# MCU.net
KiCad netlist of a schematic drawn in Altium Designer
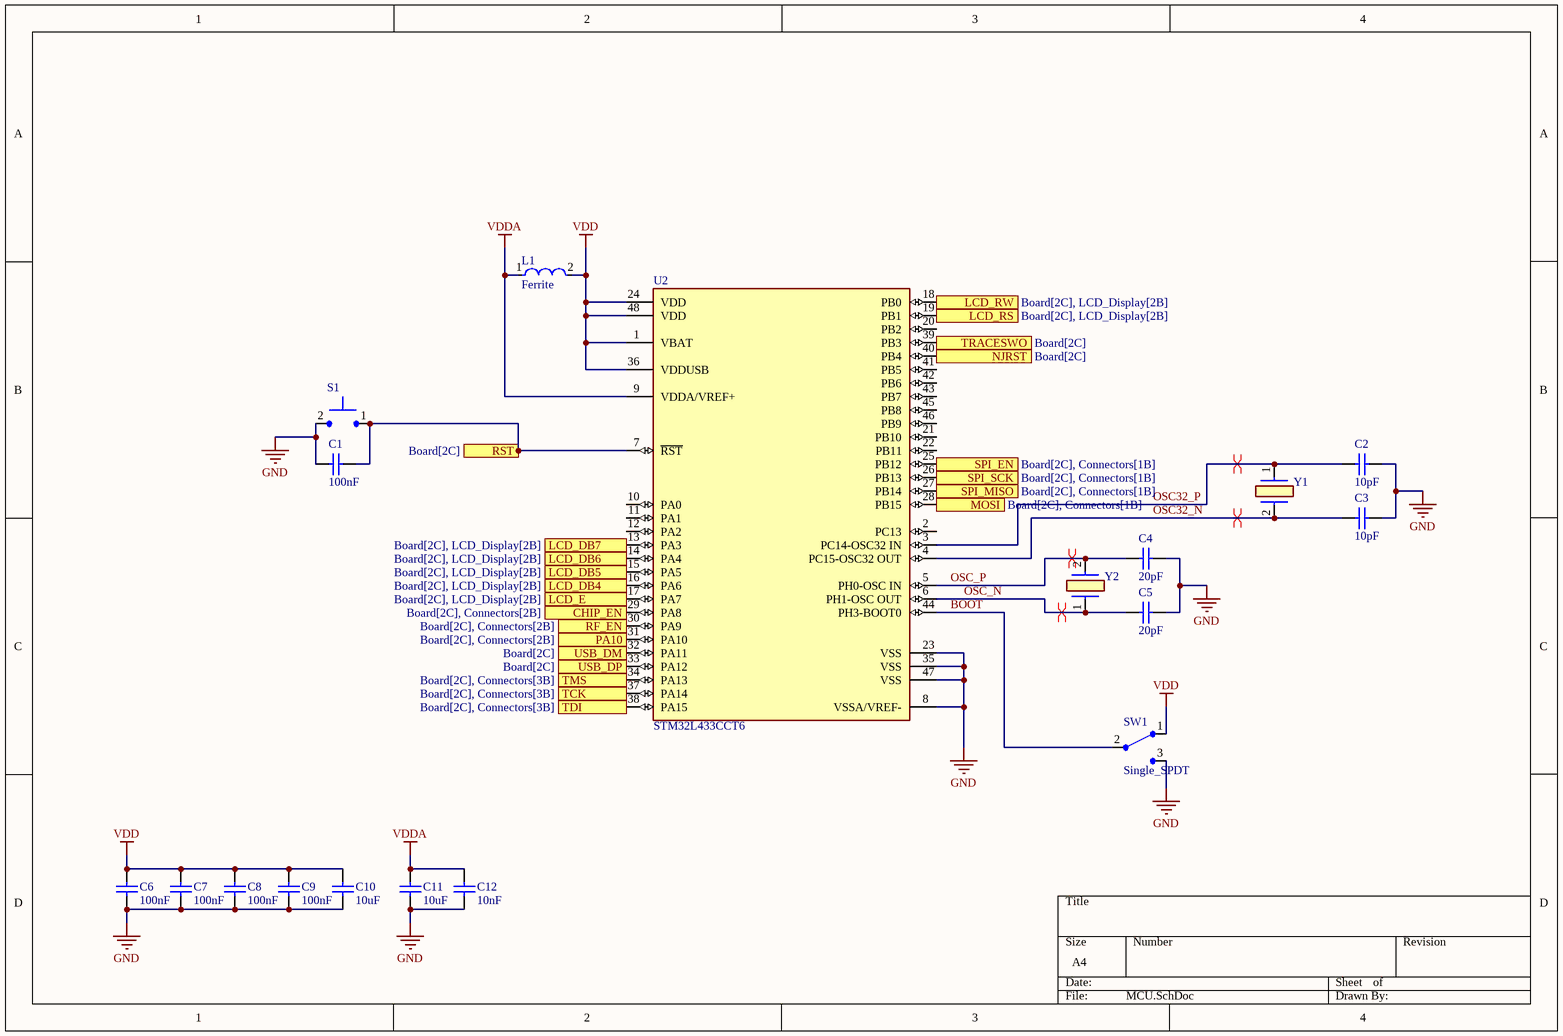
[diagram p0: MCU.SchDoc]

(export (version "E")
  (design (tool "Eeschema 10.0.6"))
  (components
    (comp (ref "C1")
      (value "100nF")
      (footprint "CAP_0402")
      (fields (field (name "MANUFACTURER") "Murata") (field (name "PART NUMBER") "GRM155R71E103KA01D"))
      (libsource (lib "schematics") (part "Capacitor"))
    )
    (comp (ref "C2")
      (value "10pF")
      (footprint "CAP_0402")
      (fields (field (name "MANUFACTURER") "Murata") (field (name "PART NUMBER") "GRM155R71E103KA01D"))
      (libsource (lib "schematics") (part "Capacitor"))
    )
    (comp (ref "C3")
      (value "10pF")
      (footprint "CAP_0402")
      (fields (field (name "MANUFACTURER") "Murata") (field (name "PART NUMBER") "GRM155R71E103KA01D"))
      (libsource (lib "schematics") (part "Capacitor"))
    )
    (comp (ref "C4")
      (value "20pF")
      (footprint "CAP_0402")
      (fields (field (name "MANUFACTURER") "Murata") (field (name "PART NUMBER") "GRM155R71E103KA01D"))
      (libsource (lib "schematics") (part "Capacitor"))
    )
    (comp (ref "C5")
      (value "20pF")
      (footprint "CAP_0402")
      (fields (field (name "MANUFACTURER") "Murata") (field (name "PART NUMBER") "GRM155R71E103KA01D"))
      (libsource (lib "schematics") (part "Capacitor"))
    )
    (comp (ref "C6")
      (value "100nF")
      (footprint "CAP_0402")
      (fields (field (name "MANUFACTURER") "Murata") (field (name "PART NUMBER") "GRM155R71E103KA01D"))
      (libsource (lib "schematics") (part "Capacitor"))
    )
    (comp (ref "C7")
      (value "100nF")
      (footprint "CAP_0402")
      (fields (field (name "MANUFACTURER") "Murata") (field (name "PART NUMBER") "GRM155R71E103KA01D"))
      (libsource (lib "schematics") (part "Capacitor"))
    )
    (comp (ref "C8")
      (value "100nF")
      (footprint "CAP_0402")
      (fields (field (name "MANUFACTURER") "Murata") (field (name "PART NUMBER") "GRM155R71E103KA01D"))
      (libsource (lib "schematics") (part "Capacitor"))
    )
    (comp (ref "C9")
      (value "100nF")
      (footprint "CAP_0402")
      (fields (field (name "MANUFACTURER") "Murata") (field (name "PART NUMBER") "GRM155R71E103KA01D"))
      (libsource (lib "schematics") (part "Capacitor"))
    )
    (comp (ref "C10")
      (value "10uF")
      (footprint "CAP_0402")
      (fields (field (name "MANUFACTURER") "Murata") (field (name "PART NUMBER") "GRM155R71E103KA01D"))
      (libsource (lib "schematics") (part "Capacitor"))
    )
    (comp (ref "C11")
      (value "10uF")
      (footprint "CAP_0402")
      (fields (field (name "MANUFACTURER") "Murata") (field (name "PART NUMBER") "GRM155R71E103KA01D"))
      (libsource (lib "schematics") (part "Capacitor"))
    )
    (comp (ref "C12")
      (value "10nF")
      (footprint "CAP_0402")
      (fields (field (name "MANUFACTURER") "Murata") (field (name "PART NUMBER") "GRM155R71E103KA01D"))
      (libsource (lib "schematics") (part "Capacitor"))
    )
    (comp (ref "L1")
      (value "Ferrite")
      (footprint "FP-LQW18AN_00-MFG")
      (fields (field (name "TOLERANCE") "2%"))
      (libsource (lib "schematics") (part "Ferrite_bead"))
    )
    (comp (ref "S1")
      (value "Generic 2-pin push button")
      (libsource (lib "schematics") (part "Push_btn_2pin"))
    )
    (comp (ref "SW1") (value "Single_SPDT") (libsource (lib "schematics") (part "Single_SPDT")))
    (comp (ref "U2")
      (value "STM32L433CCT6")
      (footprint "FP-LQFP48-5B-MFG")
      (description "IC MCU 32BIT 256KB FLASH 48LQFP")
      (fields
        (field (name "MANUFACTURER") "STMicroelectronics")
        (field (name "OCTOPART") "https://octopart.com/stm32l433cct6-stmicroelectronics-71093511")
      )
      (libsource (lib "schematics") (part "STM32L433CCT6"))
    )
    (comp (ref "Y1")
      (value "ECS-.320-12.5-13X")
      (footprint "SamacSys:ECS32012513X")
      (description "Crystal or Oscillator")
      (fields (field (name "MOUSER PART NUMBER") "520-ECS-32-12.5-13X"))
      (libsource (lib "schematics") (part "ECS-.320-12.5-13X"))
    )
    (comp (ref "Y2")
      (value "NX3225GD-8MHZ-STD-CRA-3")
      (footprint "SamacSys:NX3225GD8MHZSTDCRA3")
      (description "Crystal or Oscillator")
      (fields (field (name "MOUSER PART NUMBER") "344-NX3225GD8MCRA3"))
      (libsource (lib "schematics") (part "NX3225GD-8MHZ-STD-CRA-3"))
    )
  )
  (nets
    (net (code "1") (name "/BOOT") (class "Default")
      (node (ref "SW1") (pin "2") (pinfunction "2_2") (pintype "passive"))
      (node (ref "U2") (pin "44") (pinfunction "PH3-BOOT0_44") (pintype "bidirectional"))
    )
    (net (code "2") (name "/CHIP_EN") (class "Default")
      (node (ref "U2") (pin "29") (pinfunction "PA8_29") (pintype "bidirectional"))
    )
    (net (code "3") (name "/LCD_DB4") (class "Default")
      (node (ref "U2") (pin "16") (pinfunction "PA6_16") (pintype "bidirectional"))
    )
    (net (code "4") (name "/LCD_DB5") (class "Default")
      (node (ref "U2") (pin "15") (pinfunction "PA5_15") (pintype "bidirectional"))
    )
    (net (code "5") (name "/LCD_DB6") (class "Default")
      (node (ref "U2") (pin "14") (pinfunction "PA4_14") (pintype "bidirectional"))
    )
    (net (code "6") (name "/LCD_DB7") (class "Default")
      (node (ref "U2") (pin "13") (pinfunction "PA3_13") (pintype "bidirectional"))
    )
    (net (code "7") (name "/LCD_E") (class "Default")
      (node (ref "U2") (pin "17") (pinfunction "PA7_17") (pintype "bidirectional"))
    )
    (net (code "8") (name "/LCD_RS") (class "Default")
      (node (ref "U2") (pin "19") (pinfunction "PB1_19") (pintype "bidirectional"))
    )
    (net (code "9") (name "/LCD_RW") (class "Default")
      (node (ref "U2") (pin "18") (pinfunction "PB0_18") (pintype "bidirectional"))
    )
    (net (code "10") (name "/MOSI") (class "Default")
      (node (ref "U2") (pin "28") (pinfunction "PB15_28") (pintype "bidirectional"))
    )
    (net (code "11") (name "/NJRST") (class "Default")
      (node (ref "U2") (pin "40") (pinfunction "PB4_40") (pintype "bidirectional"))
    )
    (net (code "12") (name "/OSC32_N") (class "Default")
      (node (ref "C3") (pin "1") (pinfunction "1_1") (pintype "passive"))
      (node (ref "U2") (pin "4") (pinfunction "PC15-OSC32_OUT_4") (pintype "bidirectional"))
      (node (ref "Y1") (pin "2") (pinfunction "CRYSTAL_2_2") (pintype "passive"))
    )
    (net (code "13") (name "/OSC32_P") (class "Default")
      (node (ref "C2") (pin "1") (pinfunction "1_1") (pintype "passive"))
      (node (ref "U2") (pin "3") (pinfunction "PC14-OSC32_IN_3") (pintype "bidirectional"))
      (node (ref "Y1") (pin "1") (pintype "passive"))
    )
    (net (code "14") (name "/OSC_N") (class "Default")
      (node (ref "C5") (pin "1") (pinfunction "1_1") (pintype "passive"))
      (node (ref "U2") (pin "6") (pinfunction "PH1-OSC_OUT_6") (pintype "bidirectional"))
      (node (ref "Y2") (pin "1") (pinfunction "1_1") (pintype "passive"))
    )
    (net (code "15") (name "/OSC_P") (class "Default")
      (node (ref "C4") (pin "1") (pinfunction "1_1") (pintype "passive"))
      (node (ref "U2") (pin "5") (pinfunction "PH0-OSC_IN_5") (pintype "bidirectional"))
      (node (ref "Y2") (pin "2") (pinfunction "2_2") (pintype "passive"))
    )
    (net (code "16") (name "/PA10") (class "Default")
      (node (ref "U2") (pin "31") (pinfunction "PA10_31") (pintype "bidirectional"))
    )
    (net (code "17") (name "/RF_EN") (class "Default")
      (node (ref "U2") (pin "30") (pinfunction "PA9_30") (pintype "bidirectional"))
    )
    (net (code "18") (name "/RST") (class "Default")
      (node (ref "C1") (pin "2") (pinfunction "2_2") (pintype "passive"))
      (node (ref "S1") (pin "1") (pinfunction "1_1") (pintype "passive"))
      (node (ref "U2") (pin "7") (pinfunction "~{RST}_7") (pintype "bidirectional"))
    )
    (net (code "19") (name "/SPI_EN") (class "Default")
      (node (ref "U2") (pin "25") (pinfunction "PB12_25") (pintype "bidirectional"))
    )
    (net (code "20") (name "/SPI_MISO") (class "Default")
      (node (ref "U2") (pin "27") (pinfunction "PB14_27") (pintype "bidirectional"))
    )
    (net (code "21") (name "/SPI_SCK") (class "Default")
      (node (ref "U2") (pin "26") (pinfunction "PB13_26") (pintype "bidirectional"))
    )
    (net (code "22") (name "/TCK") (class "Default")
      (node (ref "U2") (pin "37") (pinfunction "PA14_37") (pintype "bidirectional"))
    )
    (net (code "23") (name "/TDI") (class "Default")
      (node (ref "U2") (pin "38") (pinfunction "PA15_38") (pintype "bidirectional"))
    )
    (net (code "24") (name "/TMS") (class "Default")
      (node (ref "U2") (pin "34") (pinfunction "PA13_34") (pintype "bidirectional"))
    )
    (net (code "25") (name "/TRACESWO") (class "Default")
      (node (ref "U2") (pin "39") (pinfunction "PB3_39") (pintype "bidirectional"))
    )
    (net (code "26") (name "/USB_DM") (class "Default")
      (node (ref "U2") (pin "32") (pinfunction "PA11_32") (pintype "bidirectional"))
    )
    (net (code "27") (name "/USB_DP") (class "Default")
      (node (ref "U2") (pin "33") (pinfunction "PA12_33") (pintype "bidirectional"))
    )
    (net (code "28") (name "GND") (class "Default")
      (node (ref "C1") (pin "1") (pinfunction "1_1") (pintype "passive"))
      (node (ref "C10") (pin "1") (pinfunction "1_1") (pintype "passive"))
      (node (ref "C11") (pin "1") (pinfunction "1_1") (pintype "passive"))
      (node (ref "C12") (pin "1") (pinfunction "1_1") (pintype "passive"))
      (node (ref "C2") (pin "2") (pinfunction "2_2") (pintype "passive"))
      (node (ref "C3") (pin "2") (pinfunction "2_2") (pintype "passive"))
      (node (ref "C4") (pin "2") (pinfunction "2_2") (pintype "passive"))
      (node (ref "C5") (pin "2") (pinfunction "2_2") (pintype "passive"))
      (node (ref "C6") (pin "1") (pinfunction "1_1") (pintype "passive"))
      (node (ref "C7") (pin "1") (pinfunction "1_1") (pintype "passive"))
      (node (ref "C8") (pin "1") (pinfunction "1_1") (pintype "passive"))
      (node (ref "C9") (pin "1") (pinfunction "1_1") (pintype "passive"))
      (node (ref "S1") (pin "2") (pinfunction "2_2") (pintype "passive"))
      (node (ref "SW1") (pin "3") (pinfunction "3_3") (pintype "passive"))
      (node (ref "U2") (pin "23") (pinfunction "VSS_23") (pintype "power_in"))
      (node (ref "U2") (pin "35") (pinfunction "VSS_35") (pintype "power_in"))
      (node (ref "U2") (pin "47") (pinfunction "VSS_47") (pintype "power_in"))
      (node (ref "U2") (pin "8") (pinfunction "VSSA/VREF-_8") (pintype "power_in"))
    )
    (net (code "29") (name "VDD") (class "Default")
      (node (ref "C10") (pin "2") (pinfunction "2_2") (pintype "passive"))
      (node (ref "C6") (pin "2") (pinfunction "2_2") (pintype "passive"))
      (node (ref "C7") (pin "2") (pinfunction "2_2") (pintype "passive"))
      (node (ref "C8") (pin "2") (pinfunction "2_2") (pintype "passive"))
      (node (ref "C9") (pin "2") (pinfunction "2_2") (pintype "passive"))
      (node (ref "L1") (pin "2") (pinfunction "2_2") (pintype "passive"))
      (node (ref "SW1") (pin "1") (pinfunction "1_1") (pintype "passive"))
      (node (ref "U2") (pin "1") (pinfunction "VBAT_1") (pintype "power_in"))
      (node (ref "U2") (pin "24") (pinfunction "VDD_24") (pintype "power_in"))
      (node (ref "U2") (pin "36") (pinfunction "VDDUSB_36") (pintype "power_in"))
      (node (ref "U2") (pin "48") (pinfunction "VDD_48") (pintype "power_in"))
    )
    (net (code "30") (name "VDDA") (class "Default")
      (node (ref "C11") (pin "2") (pinfunction "2_2") (pintype "passive"))
      (node (ref "C12") (pin "2") (pinfunction "2_2") (pintype "passive"))
      (node (ref "L1") (pin "1") (pinfunction "1_1") (pintype "passive"))
      (node (ref "U2") (pin "9") (pinfunction "VDDA/VREF+_9") (pintype "power_in"))
    )
    (net (code "31") (name "unconnected-(U2-PA0-Pad10)") (class "Default")
      (node (ref "U2") (pin "10") (pinfunction "PA0_10") (pintype "bidirectional"))
    )
    (net (code "32") (name "unconnected-(U2-PA1-Pad11)") (class "Default")
      (node (ref "U2") (pin "11") (pinfunction "PA1_11") (pintype "bidirectional"))
    )
    (net (code "33") (name "unconnected-(U2-PA2-Pad12)") (class "Default")
      (node (ref "U2") (pin "12") (pinfunction "PA2_12") (pintype "bidirectional"))
    )
    (net (code "34") (name "unconnected-(U2-PB2-Pad20)") (class "Default")
      (node (ref "U2") (pin "20") (pinfunction "PB2_20") (pintype "bidirectional"))
    )
    (net (code "35") (name "unconnected-(U2-PB5-Pad41)") (class "Default")
      (node (ref "U2") (pin "41") (pinfunction "PB5_41") (pintype "bidirectional"))
    )
    (net (code "36") (name "unconnected-(U2-PB6-Pad42)") (class "Default")
      (node (ref "U2") (pin "42") (pinfunction "PB6_42") (pintype "bidirectional"))
    )
    (net (code "37") (name "unconnected-(U2-PB7-Pad43)") (class "Default")
      (node (ref "U2") (pin "43") (pinfunction "PB7_43") (pintype "bidirectional"))
    )
    (net (code "38") (name "unconnected-(U2-PB8-Pad45)") (class "Default")
      (node (ref "U2") (pin "45") (pinfunction "PB8_45") (pintype "bidirectional"))
    )
    (net (code "39") (name "unconnected-(U2-PB9-Pad46)") (class "Default")
      (node (ref "U2") (pin "46") (pinfunction "PB9_46") (pintype "bidirectional"))
    )
    (net (code "40") (name "unconnected-(U2-PB10-Pad21)") (class "Default")
      (node (ref "U2") (pin "21") (pinfunction "PB10_21") (pintype "bidirectional"))
    )
    (net (code "41") (name "unconnected-(U2-PB11-Pad22)") (class "Default")
      (node (ref "U2") (pin "22") (pinfunction "PB11_22") (pintype "bidirectional"))
    )
    (net (code "42") (name "unconnected-(U2-PC13-Pad2)") (class "Default")
      (node (ref "U2") (pin "2") (pinfunction "PC13_2") (pintype "bidirectional"))
    )
  )
)
